# E-16_LVDS_to_HDMI.net
KiCad netlist of a schematic drawn in Altium Designer
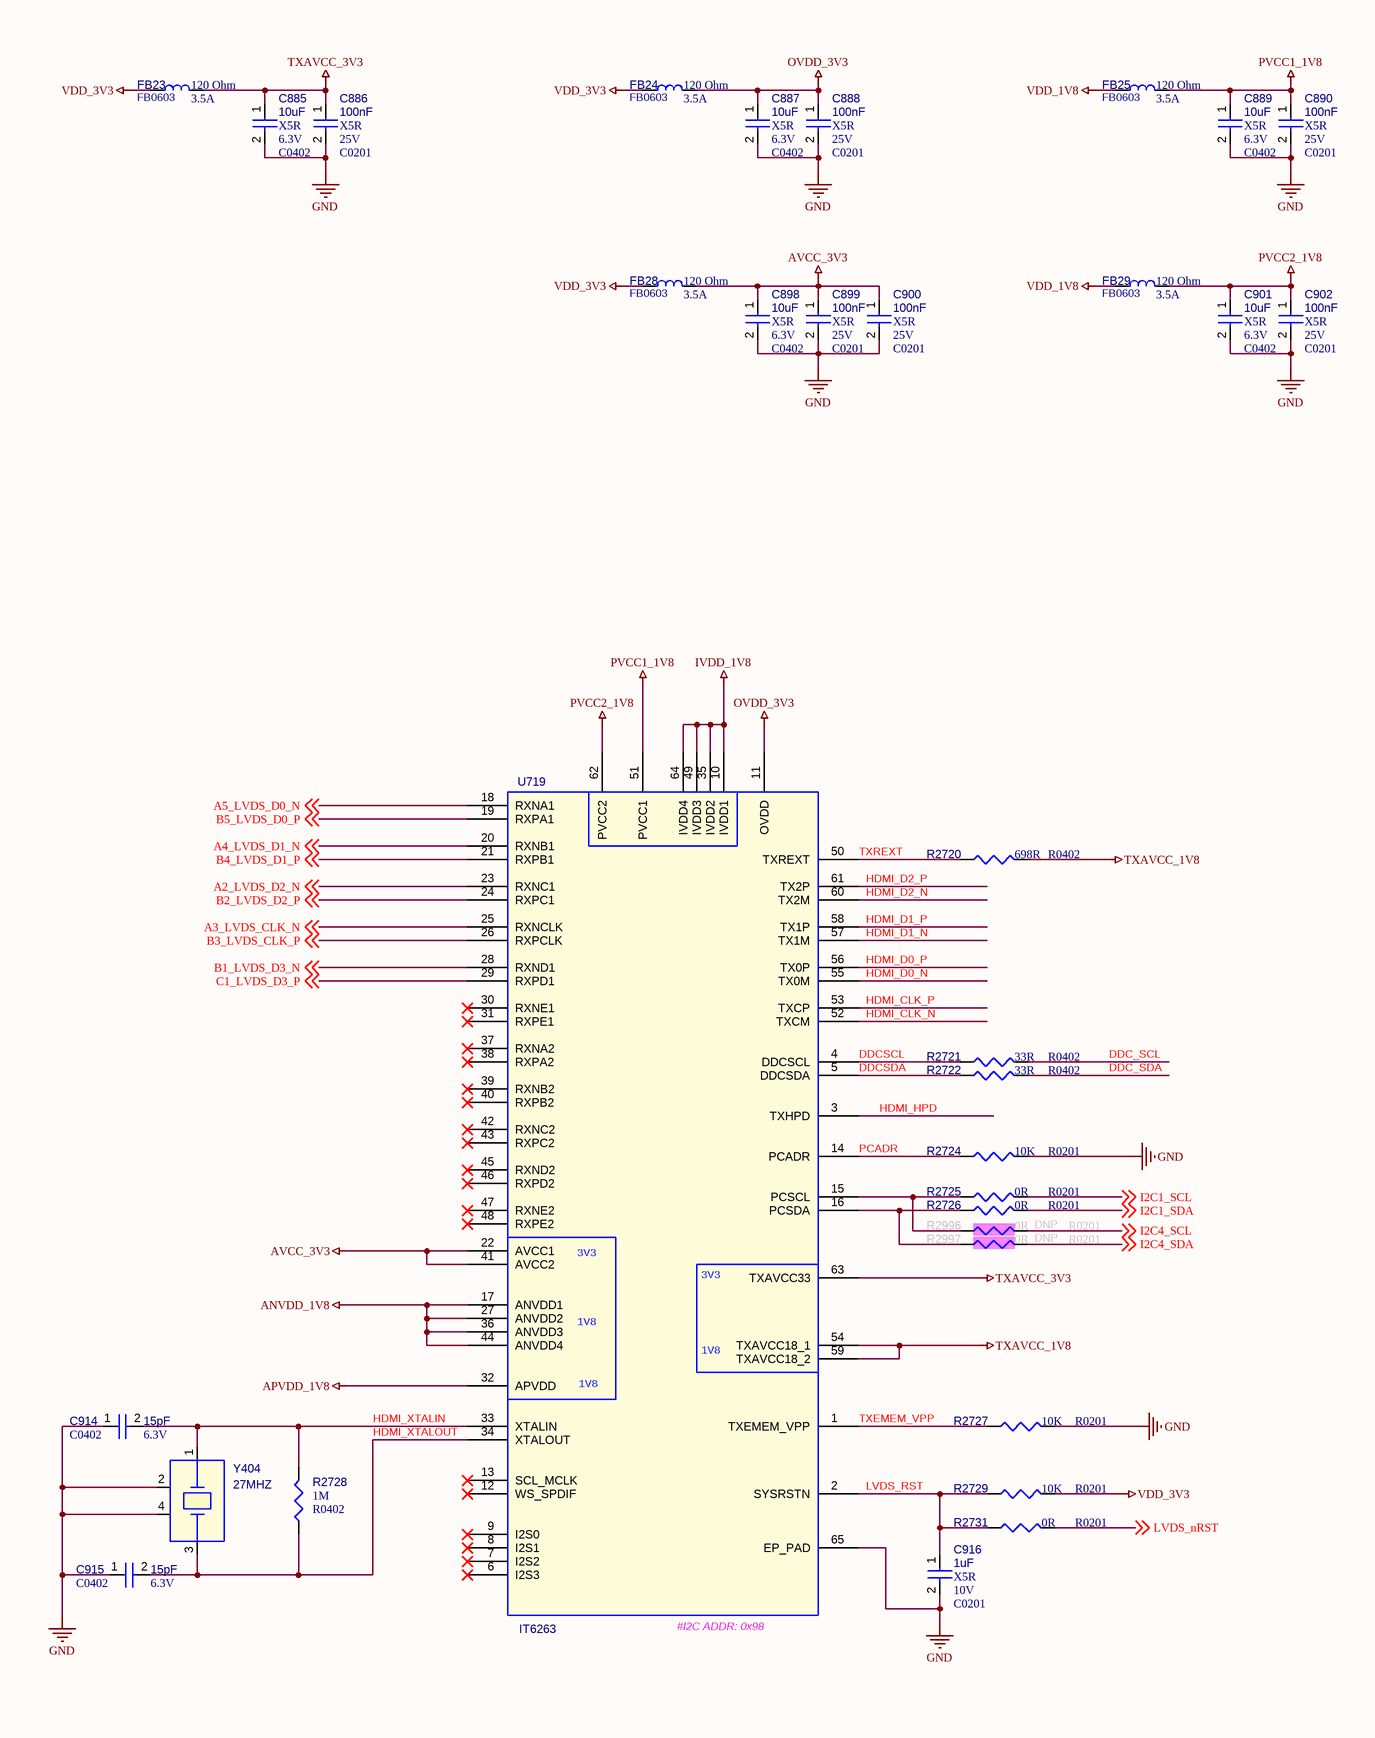
[diagram p0: E-16 LVDS to HDMI.SchDoc, left]
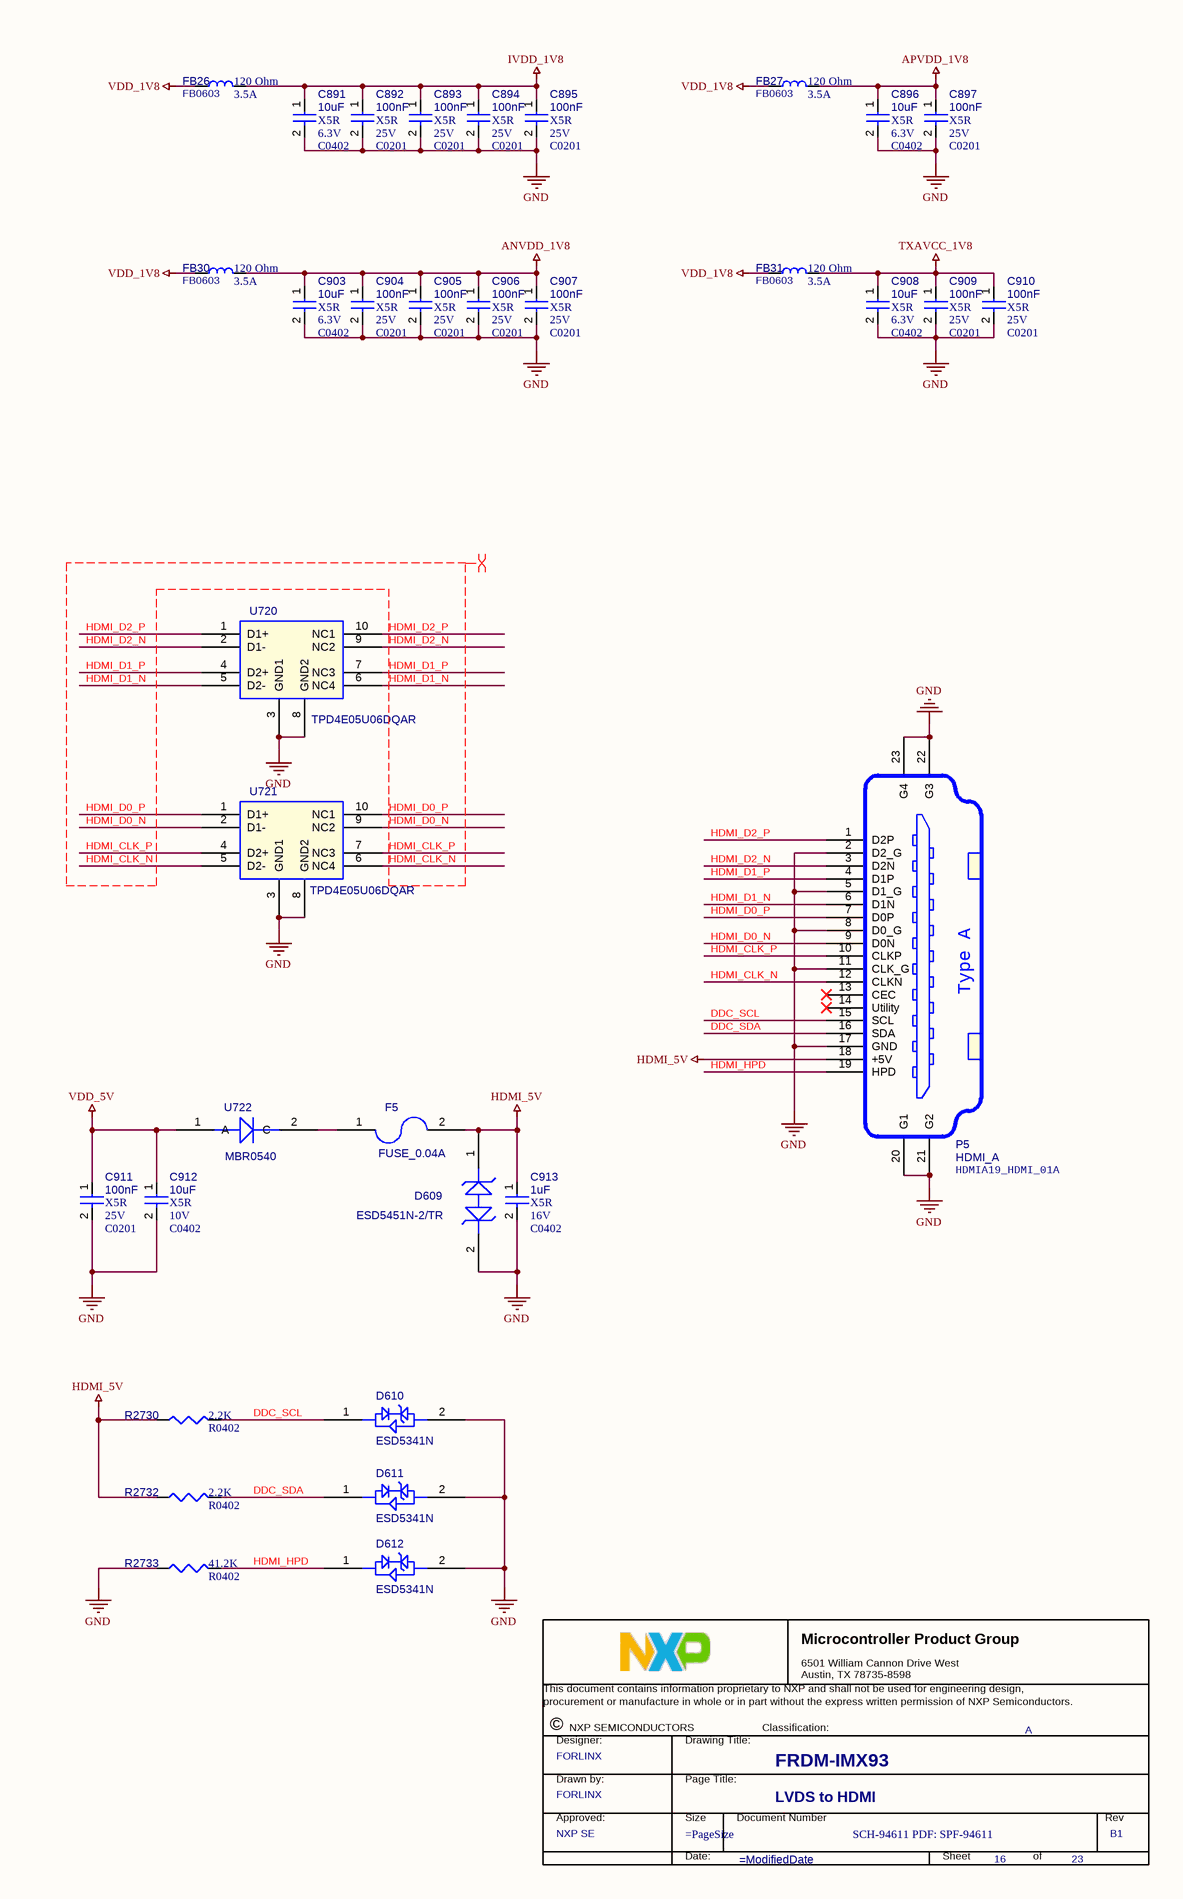
[diagram p1: E-16 LVDS to HDMI.SchDoc, right]

(export (version "E")
  (design (tool "Eeschema 10.0.6"))
  (components
    (comp (ref "C885")
      (value "10uF")
      (footprint "C0402")
      (description "0402,10uF,6.3V,+/-20%,X5R")
      (fields
        (field (name "VOLTAGE") "6.3V")
        (field (name "PCB FOOTPRINT") "C0402")
        (field (name "DIELECTRIC") "X5R")
        (field (name "MANUFACTURER") "FH(风华)")
        (field (name "TOLERANCE") "±10%")
        (field (name "CREATED BY") "JJJ")
      )
      (libsource (lib "*") (part "CAP NP"))
    )
    (comp (ref "C886")
      (value "100nF")
      (footprint "C0201")
      (description "0201,100nF,25V,+/-10%,X5R")
      (fields
        (field (name "VOLTAGE") "25V")
        (field (name "PCB FOOTPRINT") "C0201")
        (field (name "DIELECTRIC") "X5R")
        (field (name "TOLERANCE") "±10%")
        (field (name "MANUFACTURER") "FH(风华)")
        (field (name "CREATED BY") "JJJ")
      )
      (libsource (lib "*") (part "CAP NP"))
    )
    (comp (ref "C887")
      (value "10uF")
      (footprint "C0402")
      (description "0402,10uF,6.3V,+/-20%,X5R")
      (fields
        (field (name "VOLTAGE") "6.3V")
        (field (name "PCB FOOTPRINT") "C0402")
        (field (name "DIELECTRIC") "X5R")
        (field (name "MANUFACTURER") "FH(风华)")
        (field (name "TOLERANCE") "±10%")
        (field (name "CREATED BY") "JJJ")
      )
      (libsource (lib "*") (part "CAP NP"))
    )
    (comp (ref "C888")
      (value "100nF")
      (footprint "C0201")
      (description "0201,100nF,25V,+/-10%,X5R")
      (fields
        (field (name "VOLTAGE") "25V")
        (field (name "PCB FOOTPRINT") "C0201")
        (field (name "DIELECTRIC") "X5R")
        (field (name "TOLERANCE") "±10%")
        (field (name "MANUFACTURER") "FH(风华)")
        (field (name "CREATED BY") "JJJ")
      )
      (libsource (lib "*") (part "CAP NP"))
    )
    (comp (ref "C889")
      (value "10uF")
      (footprint "C0402")
      (description "0402,10uF,6.3V,+/-20%,X5R")
      (fields
        (field (name "VOLTAGE") "6.3V")
        (field (name "PCB FOOTPRINT") "C0402")
        (field (name "DIELECTRIC") "X5R")
        (field (name "MANUFACTURER") "FH(风华)")
        (field (name "TOLERANCE") "±10%")
        (field (name "CREATED BY") "JJJ")
      )
      (libsource (lib "*") (part "CAP NP"))
    )
    (comp (ref "C890")
      (value "100nF")
      (footprint "C0201")
      (description "0201,100nF,25V,+/-10%,X5R")
      (fields
        (field (name "VOLTAGE") "25V")
        (field (name "PCB FOOTPRINT") "C0201")
        (field (name "DIELECTRIC") "X5R")
        (field (name "TOLERANCE") "±10%")
        (field (name "MANUFACTURER") "FH(风华)")
        (field (name "CREATED BY") "JJJ")
      )
      (libsource (lib "*") (part "CAP NP"))
    )
    (comp (ref "C891")
      (value "10uF")
      (footprint "C0402")
      (description "0402,10uF,6.3V,+/-20%,X5R")
      (fields
        (field (name "VOLTAGE") "6.3V")
        (field (name "PCB FOOTPRINT") "C0402")
        (field (name "DIELECTRIC") "X5R")
        (field (name "MANUFACTURER") "FH(风华)")
        (field (name "TOLERANCE") "±10%")
        (field (name "CREATED BY") "JJJ")
      )
      (libsource (lib "*") (part "CAP NP"))
    )
    (comp (ref "C892")
      (value "100nF")
      (footprint "C0201")
      (description "0201,100nF,25V,+/-10%,X5R")
      (fields
        (field (name "VOLTAGE") "25V")
        (field (name "PCB FOOTPRINT") "C0201")
        (field (name "DIELECTRIC") "X5R")
        (field (name "TOLERANCE") "±10%")
        (field (name "MANUFACTURER") "FH(风华)")
        (field (name "CREATED BY") "JJJ")
      )
      (libsource (lib "*") (part "CAP NP"))
    )
    (comp (ref "C893")
      (value "100nF")
      (footprint "C0201")
      (description "0201,100nF,25V,+/-10%,X5R")
      (fields
        (field (name "VOLTAGE") "25V")
        (field (name "PCB FOOTPRINT") "C0201")
        (field (name "DIELECTRIC") "X5R")
        (field (name "MANUFACTURER") "FH(风华)")
        (field (name "TOLERANCE") "±10%")
        (field (name "CREATED BY") "JJJ")
      )
      (libsource (lib "*") (part "CAP NP"))
    )
    (comp (ref "C894")
      (value "100nF")
      (footprint "C0201")
      (description "0201,100nF,25V,+/-10%,X5R")
      (fields
        (field (name "VOLTAGE") "25V")
        (field (name "PCB FOOTPRINT") "C0201")
        (field (name "DIELECTRIC") "X5R")
        (field (name "MANUFACTURER") "FH(风华)")
        (field (name "TOLERANCE") "±10%")
        (field (name "CREATED BY") "JJJ")
      )
      (libsource (lib "*") (part "CAP NP"))
    )
    (comp (ref "C895")
      (value "100nF")
      (footprint "C0201")
      (description "0201,100nF,25V,+/-10%,X5R")
      (fields
        (field (name "VOLTAGE") "25V")
        (field (name "PCB FOOTPRINT") "C0201")
        (field (name "DIELECTRIC") "X5R")
        (field (name "TOLERANCE") "±10%")
        (field (name "MANUFACTURER") "FH(风华)")
        (field (name "CREATED BY") "JJJ")
      )
      (libsource (lib "*") (part "CAP NP"))
    )
    (comp (ref "C896")
      (value "10uF")
      (footprint "C0402")
      (description "0402,10uF,6.3V,+/-20%,X5R")
      (fields
        (field (name "VOLTAGE") "6.3V")
        (field (name "PCB FOOTPRINT") "C0402")
        (field (name "DIELECTRIC") "X5R")
        (field (name "MANUFACTURER") "FH(风华)")
        (field (name "TOLERANCE") "±10%")
        (field (name "CREATED BY") "JJJ")
      )
      (libsource (lib "*") (part "CAP NP"))
    )
    (comp (ref "C897")
      (value "100nF")
      (footprint "C0201")
      (description "0201,100nF,25V,+/-10%,X5R")
      (fields
        (field (name "VOLTAGE") "25V")
        (field (name "PCB FOOTPRINT") "C0201")
        (field (name "DIELECTRIC") "X5R")
        (field (name "MANUFACTURER") "FH(风华)")
        (field (name "TOLERANCE") "±10%")
        (field (name "CREATED BY") "JJJ")
      )
      (libsource (lib "*") (part "CAP NP"))
    )
    (comp (ref "C898")
      (value "10uF")
      (footprint "C0402")
      (description "0402,10uF,6.3V,+/-20%,X5R")
      (fields
        (field (name "VOLTAGE") "6.3V")
        (field (name "PCB FOOTPRINT") "C0402")
        (field (name "DIELECTRIC") "X5R")
        (field (name "TOLERANCE") "±10%")
        (field (name "MANUFACTURER") "FH(风华)")
        (field (name "CREATED BY") "JJJ")
      )
      (libsource (lib "*") (part "CAP NP"))
    )
    (comp (ref "C899")
      (value "100nF")
      (footprint "C0201")
      (description "0201,100nF,25V,+/-10%,X5R")
      (fields
        (field (name "VOLTAGE") "25V")
        (field (name "PCB FOOTPRINT") "C0201")
        (field (name "DIELECTRIC") "X5R")
        (field (name "MANUFACTURER") "FH(风华)")
        (field (name "TOLERANCE") "±10%")
        (field (name "CREATED BY") "JJJ")
      )
      (libsource (lib "*") (part "CAP NP"))
    )
    (comp (ref "C900")
      (value "100nF")
      (footprint "C0201")
      (description "0201,100nF,25V,+/-10%,X5R")
      (fields
        (field (name "VOLTAGE") "25V")
        (field (name "PCB FOOTPRINT") "C0201")
        (field (name "DIELECTRIC") "X5R")
        (field (name "MANUFACTURER") "FH(风华)")
        (field (name "TOLERANCE") "±10%")
        (field (name "CREATED BY") "JJJ")
      )
      (libsource (lib "*") (part "CAP NP"))
    )
    (comp (ref "C901")
      (value "10uF")
      (footprint "C0402")
      (description "0402,10uF,6.3V,+/-20%,X5R")
      (fields
        (field (name "VOLTAGE") "6.3V")
        (field (name "PCB FOOTPRINT") "C0402")
        (field (name "DIELECTRIC") "X5R")
        (field (name "TOLERANCE") "±10%")
        (field (name "MANUFACTURER") "FH(风华)")
        (field (name "CREATED BY") "JJJ")
      )
      (libsource (lib "*") (part "CAP NP"))
    )
    (comp (ref "C902")
      (value "100nF")
      (footprint "C0201")
      (description "0201,100nF,25V,+/-10%,X5R")
      (fields
        (field (name "VOLTAGE") "25V")
        (field (name "PCB FOOTPRINT") "C0201")
        (field (name "DIELECTRIC") "X5R")
        (field (name "MANUFACTURER") "FH(风华)")
        (field (name "TOLERANCE") "±10%")
        (field (name "CREATED BY") "JJJ")
      )
      (libsource (lib "*") (part "CAP NP"))
    )
    (comp (ref "C903")
      (value "10uF")
      (footprint "C0402")
      (description "0402,10uF,6.3V,+/-20%,X5R")
      (fields
        (field (name "VOLTAGE") "6.3V")
        (field (name "PCB FOOTPRINT") "C0402")
        (field (name "DIELECTRIC") "X5R")
        (field (name "MANUFACTURER") "FH(风华)")
        (field (name "TOLERANCE") "±10%")
        (field (name "CREATED BY") "JJJ")
      )
      (libsource (lib "*") (part "CAP NP"))
    )
    (comp (ref "C904")
      (value "100nF")
      (footprint "C0201")
      (description "0201,100nF,25V,+/-10%,X5R")
      (fields
        (field (name "VOLTAGE") "25V")
        (field (name "PCB FOOTPRINT") "C0201")
        (field (name "DIELECTRIC") "X5R")
        (field (name "TOLERANCE") "±10%")
        (field (name "MANUFACTURER") "FH(风华)")
        (field (name "CREATED BY") "JJJ")
      )
      (libsource (lib "*") (part "CAP NP"))
    )
    (comp (ref "C905")
      (value "100nF")
      (footprint "C0201")
      (description "0201,100nF,25V,+/-10%,X5R")
      (fields
        (field (name "VOLTAGE") "25V")
        (field (name "PCB FOOTPRINT") "C0201")
        (field (name "DIELECTRIC") "X5R")
        (field (name "MANUFACTURER") "FH(风华)")
        (field (name "TOLERANCE") "±10%")
        (field (name "CREATED BY") "JJJ")
      )
      (libsource (lib "*") (part "CAP NP"))
    )
    (comp (ref "C906")
      (value "100nF")
      (footprint "C0201")
      (description "0201,100nF,25V,+/-10%,X5R")
      (fields
        (field (name "VOLTAGE") "25V")
        (field (name "PCB FOOTPRINT") "C0201")
        (field (name "DIELECTRIC") "X5R")
        (field (name "MANUFACTURER") "FH(风华)")
        (field (name "TOLERANCE") "±10%")
        (field (name "CREATED BY") "JJJ")
      )
      (libsource (lib "*") (part "CAP NP"))
    )
    (comp (ref "C907")
      (value "100nF")
      (footprint "C0201")
      (description "0201,100nF,25V,+/-10%,X5R")
      (fields
        (field (name "VOLTAGE") "25V")
        (field (name "PCB FOOTPRINT") "C0201")
        (field (name "DIELECTRIC") "X5R")
        (field (name "TOLERANCE") "±10%")
        (field (name "MANUFACTURER") "FH(风华)")
        (field (name "CREATED BY") "JJJ")
      )
      (libsource (lib "*") (part "CAP NP"))
    )
    (comp (ref "C908")
      (value "10uF")
      (footprint "C0402")
      (description "0402,10uF,6.3V,+/-20%,X5R")
      (fields
        (field (name "VOLTAGE") "6.3V")
        (field (name "PCB FOOTPRINT") "C0402")
        (field (name "DIELECTRIC") "X5R")
        (field (name "MANUFACTURER") "FH(风华)")
        (field (name "TOLERANCE") "±10%")
        (field (name "CREATED BY") "JJJ")
      )
      (libsource (lib "*") (part "CAP NP"))
    )
    (comp (ref "C909")
      (value "100nF")
      (footprint "C0201")
      (description "0201,100nF,25V,+/-10%,X5R")
      (fields
        (field (name "VOLTAGE") "25V")
        (field (name "PCB FOOTPRINT") "C0201")
        (field (name "DIELECTRIC") "X5R")
        (field (name "TOLERANCE") "±10%")
        (field (name "MANUFACTURER") "FH(风华)")
        (field (name "CREATED BY") "JJJ")
      )
      (libsource (lib "*") (part "CAP NP"))
    )
    (comp (ref "C910")
      (value "100nF")
      (footprint "C0201")
      (description "0201,100nF,25V,+/-10%,X5R")
      (fields
        (field (name "VOLTAGE") "25V")
        (field (name "PCB FOOTPRINT") "C0201")
        (field (name "DIELECTRIC") "X5R")
        (field (name "TOLERANCE") "±10%")
        (field (name "MANUFACTURER") "FH(风华)")
        (field (name "CREATED BY") "JJJ")
      )
      (libsource (lib "*") (part "CAP NP"))
    )
    (comp (ref "C911")
      (value "100nF")
      (footprint "C0201")
      (description "0201,100nF,25V,+/-10%,X5R")
      (fields
        (field (name "VOLTAGE") "25V")
        (field (name "PCB FOOTPRINT") "C0201")
        (field (name "DIELECTRIC") "X5R")
        (field (name "MANUFACTURER") "FH(风华)")
        (field (name "TOLERANCE") "±10%")
        (field (name "CREATED BY") "JJJ")
      )
      (libsource (lib "*") (part "CAP NP"))
    )
    (comp (ref "C912")
      (value "10uF")
      (footprint "C0402")
      (description "0402,10uF,6.3V,+/-20%,X5R")
      (fields
        (field (name "VOLTAGE") "10V")
        (field (name "PCB FOOTPRINT") "C0402")
        (field (name "DIELECTRIC") "X5R")
        (field (name "MANUFACTURER") "FH(风华)")
        (field (name "TOLERANCE") "±10%")
        (field (name "CREATED BY") "JJJ")
      )
      (libsource (lib "*") (part "CAP NP"))
    )
    (comp (ref "C913")
      (value "1uF")
      (footprint "C0402")
      (description "0402,1uF,16V,+/-10%,X5R")
      (fields
        (field (name "VOLTAGE") "16V")
        (field (name "PCB FOOTPRINT") "C0402")
        (field (name "DIELECTRIC") "X5R")
        (field (name "TOLERANCE") "±10%")
        (field (name "MANUFACTURER") "FH(风华)")
        (field (name "CREATED BY") "JJJ")
      )
      (libsource (lib "*") (part "CAP NP"))
    )
    (comp (ref "C914")
      (value "15pF")
      (footprint "C0402")
      (description "0402,15pF,50V,+/-5%,NPO")
      (fields
        (field (name "VOLTAGE") "6.3V")
        (field (name "PCB FOOTPRINT") "C0402")
        (field (name "TOLERANCE") "±10%")
        (field (name "MANUFACTURER") "FH(风华)")
        (field (name "CREATED BY") "JJJ")
      )
      (libsource (lib "*") (part "CAP NP"))
    )
    (comp (ref "C915")
      (value "15pF")
      (footprint "C0402")
      (description "0402,15pF,50V,+/-5%,NPO")
      (fields
        (field (name "VOLTAGE") "6.3V")
        (field (name "PCB FOOTPRINT") "C0402")
        (field (name "TOLERANCE") "±10%")
        (field (name "MANUFACTURER") "FH(风华)")
        (field (name "CREATED BY") "JJJ")
      )
      (libsource (lib "*") (part "CAP NP"))
    )
    (comp (ref "C916")
      (value "1uF")
      (footprint "C0201")
      (description "0201,1uF,10V,+/-20%,X5R")
      (fields
        (field (name "VOLTAGE") "10V")
        (field (name "PCB FOOTPRINT") "C0201")
        (field (name "DIELECTRIC") "X5R")
        (field (name "MANUFACTURER") "FH(风华)")
        (field (name "TOLERANCE") "±10%")
        (field (name "CREATED BY") "JJJ")
      )
      (libsource (lib "*") (part "CAP NP"))
    )
    (comp (ref "D609")
      (value "ESD5451N-2/TR")
      (footprint "0402TVS")
      (libsource (lib "*") (part "ESD5451N-2/TR"))
    )
    (comp (ref "D610")
      (value "ESD5341N")
      (footprint "0402TVS")
      (description "ESD5341N-2/TR")
      (libsource (lib "*") (part "ESD5341N"))
    )
    (comp (ref "D611")
      (value "ESD5341N")
      (footprint "0402TVS")
      (description "ESD5341N-2/TR")
      (libsource (lib "*") (part "ESD5341N"))
    )
    (comp (ref "D612")
      (value "ESD5341N")
      (footprint "0402TVS")
      (description "ESD5341N-2/TR")
      (libsource (lib "*") (part "ESD5341N"))
    )
    (comp (ref "F5")
      (value "FUSE_0.04A")
      (footprint "F0603")
      (description "0603,0.04A/0.12A,15V,ASMD0603-004")
      (libsource (lib "*") (part "FUSE_0.5A"))
    )
    (comp (ref "FB23")
      (value "120 Ohm")
      (footprint "FB0603")
      (description "0603,120Ohm@100MHZ,3A")
      (fields (field (name "ELECTRIC CURRENT") "3.5A") (field (name "PCB FOOTPRINT") "FB0603"))
      (libsource (lib "*") (part "FB0402,120ohm,1.3A"))
    )
    (comp (ref "FB24")
      (value "120 Ohm")
      (footprint "FB0603")
      (description "0603,120Ohm@100MHZ,3A")
      (fields (field (name "ELECTRIC CURRENT") "3.5A") (field (name "PCB FOOTPRINT") "FB0603"))
      (libsource (lib "*") (part "FB0402,120ohm,1.3A"))
    )
    (comp (ref "FB25")
      (value "120 Ohm")
      (footprint "FB0603")
      (description "0603,120Ohm@100MHZ,3A")
      (fields (field (name "ELECTRIC CURRENT") "3.5A") (field (name "PCB FOOTPRINT") "FB0603"))
      (libsource (lib "*") (part "FB0402,120ohm,1.3A"))
    )
    (comp (ref "FB26")
      (value "120 Ohm")
      (footprint "FB0603")
      (description "0603,120Ohm@100MHZ,3A")
      (fields (field (name "ELECTRIC CURRENT") "3.5A") (field (name "PCB FOOTPRINT") "FB0603"))
      (libsource (lib "*") (part "FB0402,120ohm,1.3A"))
    )
    (comp (ref "FB27")
      (value "120 Ohm")
      (footprint "FB0603")
      (description "0603,120Ohm@100MHZ,3A")
      (fields (field (name "ELECTRIC CURRENT") "3.5A") (field (name "PCB FOOTPRINT") "FB0603"))
      (libsource (lib "*") (part "FB0402,120ohm,1.3A"))
    )
    (comp (ref "FB28")
      (value "120 Ohm")
      (footprint "FB0603")
      (description "0603,120Ohm@100MHZ,3A")
      (fields (field (name "ELECTRIC CURRENT") "3.5A") (field (name "PCB FOOTPRINT") "FB0603"))
      (libsource (lib "*") (part "FB0402,120ohm,1.3A"))
    )
    (comp (ref "FB29")
      (value "120 Ohm")
      (footprint "FB0603")
      (description "0603,120Ohm@100MHZ,3A")
      (fields (field (name "ELECTRIC CURRENT") "3.5A") (field (name "PCB FOOTPRINT") "FB0603"))
      (libsource (lib "*") (part "FB0402,120ohm,1.3A"))
    )
    (comp (ref "FB30")
      (value "120 Ohm")
      (footprint "FB0603")
      (description "0603,120Ohm@100MHZ,3A")
      (fields (field (name "ELECTRIC CURRENT") "3.5A") (field (name "PCB FOOTPRINT") "FB0603"))
      (libsource (lib "*") (part "FB0402,120ohm,1.3A"))
    )
    (comp (ref "FB31")
      (value "120 Ohm")
      (footprint "FB0603")
      (description "0603,120Ohm@100MHZ,3A")
      (fields (field (name "ELECTRIC CURRENT") "3.5A") (field (name "PCB FOOTPRINT") "FB0603"))
      (libsource (lib "*") (part "FB0402,120ohm,1.3A"))
    )
    (comp (ref "P5")
      (value "HDMI_A")
      (footprint "HDMIA19_HDMI_01A")
      (description "HDMI-A")
      (fields
        (field (name "MANUFACTURER") "旺科达")
        (field (name "MANUFACTURER PART NUMBER") "HDMI_01A")
        (field (name "PCB FOOTPRINT") "HDMIA19_HDMI_01A")
        (field (name "CREATED BY") "JJJ")
      )
      (libsource (lib "*") (part "HDMI_A"))
    )
    (comp (ref "R2720")
      (value "698R")
      (footprint "R0402")
      (description "0402,698Ohm,+/-1%")
      (fields (field (name "PCB FOOTPRINT") "R0402"))
      (libsource (lib "*") (part "R0402,4.7K_Dup1"))
    )
    (comp (ref "R2721")
      (value "33R")
      (footprint "R0402")
      (description "0402,33Ohm,+/-1%")
      (fields (field (name "PCB FOOTPRINT") "R0402"))
      (libsource (lib "*") (part "R0402,4.7K_Dup1"))
    )
    (comp (ref "R2722")
      (value "33R")
      (footprint "R0402")
      (description "0402,33Ohm,+/-1%")
      (fields (field (name "PCB FOOTPRINT") "R0402"))
      (libsource (lib "*") (part "R0402,4.7K_Dup1"))
    )
    (comp (ref "R2724")
      (value "10K")
      (footprint "R0201")
      (description "0201,10K,+/-5%")
      (fields (field (name "PCB FOOTPRINT") "R0201"))
      (libsource (lib "*") (part "R0402,4.7K_Dup1"))
    )
    (comp (ref "R2725")
      (value "0R")
      (footprint "R0201")
      (description "0201,0Ohm,+/-5%")
      (fields (field (name "PCB FOOTPRINT") "R0201"))
      (libsource (lib "*") (part "R0402,4.7K_Dup1"))
    )
    (comp (ref "R2726")
      (value "0R")
      (footprint "R0201")
      (description "0201,0Ohm,+/-5%")
      (fields (field (name "PCB FOOTPRINT") "R0201"))
      (libsource (lib "*") (part "R0402,4.7K_Dup1"))
    )
    (comp (ref "R2727")
      (value "10K")
      (footprint "R0201")
      (description "0201,10K,+/-5%")
      (fields (field (name "PCB FOOTPRINT") "R0201"))
      (libsource (lib "*") (part "R0402,4.7K_Dup1"))
    )
    (comp (ref "R2728")
      (value "1M")
      (footprint "R0402")
      (description "0402,1M,+/-1%")
      (fields (field (name "PCB FOOTPRINT") "R0402"))
      (libsource (lib "*") (part "R0402,4.7K_Dup1"))
    )
    (comp (ref "R2729")
      (value "10K")
      (footprint "R0201")
      (description "0201,10K,+/-5%")
      (fields (field (name "PCB FOOTPRINT") "R0201"))
      (libsource (lib "*") (part "R0402,4.7K_Dup1"))
    )
    (comp (ref "R2730")
      (value "2.2K")
      (footprint "R0402")
      (description "0402,2.2K,+/-1%")
      (fields (field (name "PCB FOOTPRINT") "R0402"))
      (libsource (lib "*") (part "R0402,4.7K_Dup1"))
    )
    (comp (ref "R2731")
      (value "0R")
      (footprint "R0201")
      (description "0201,0Ohm,+/-5%")
      (fields (field (name "PCB FOOTPRINT") "R0201"))
      (libsource (lib "*") (part "R0402,4.7K_Dup1"))
    )
    (comp (ref "R2732")
      (value "2.2K")
      (footprint "R0402")
      (description "0402,2.2K,+/-1%")
      (fields (field (name "PCB FOOTPRINT") "R0402"))
      (libsource (lib "*") (part "R0402,4.7K_Dup1"))
    )
    (comp (ref "R2733")
      (value "41.2K")
      (footprint "R0402")
      (description "0402,41.2K,+/-1%")
      (fields (field (name "PCB FOOTPRINT") "R0402"))
      (libsource (lib "*") (part "R0402,4.7K_Dup1"))
    )
    (comp (ref "R2996")
      (value "0R")
      (footprint "R0201")
      (description "0201,0Ohm,+/-5%")
      (fields (field (name "PCB FOOTPRINT") "R0201") (field (name "ASSY_OPT") "DNP"))
      (libsource (lib "*") (part "R0402,4.7K_Dup1"))
    )
    (comp (ref "R2997")
      (value "0R")
      (footprint "R0201")
      (description "0201,0Ohm,+/-5%")
      (fields (field (name "PCB FOOTPRINT") "R0201") (field (name "ASSY_OPT") "DNP"))
      (libsource (lib "*") (part "R0402,4.7K_Dup1"))
    )
    (comp (ref "U719")
      (value "IT6263")
      (footprint "qfn64_0p5_9x9_157ep")
      (description "IT6263FN,QFN64,9*9mm,LVDS to HDMI")
      (libsource (lib "*") (part "IT6263"))
    )
    (comp (ref "U720")
      (value "TPD4E05U06DQAR")
      (footprint "USON-10")
      (description "TPD4E05U06DQAR,USON")
      (libsource (lib "*") (part "TPD4E05U06DQAR_10"))
    )
    (comp (ref "U721")
      (value "TPD4E05U06DQAR")
      (footprint "USON-10")
      (description "TPD4E05U06DQAR,USON")
      (libsource (lib "*") (part "TPD4E05U06DQAR_5"))
    )
    (comp (ref "U722")
      (value "MBR0540")
      (footprint "SOD_123")
      (description "MBR0540,SOD123")
      (libsource (lib "*") (part "MBR0540_0"))
    )
    (comp (ref "Y404")
      (value "27MHZ")
      (footprint "xtlosc4_3p2x2p5mm_sm")
      (description "Crystal,27MHZ,4P,3.2*2.5mm,+/-20ppm,20pf")
      (libsource (lib "*") (part "XTAL_13"))
    )
  )
  (nets
    (net (code "1") (name "/DDCSCL") (class "Default")
      (node (ref "R2721") (pin "1") (pinfunction "1_1") (pintype "passive"))
      (node (ref "U719") (pin "4") (pinfunction "DDCSCL_4") (pintype "passive"))
    )
    (net (code "2") (name "/DDCSDA") (class "Default")
      (node (ref "R2722") (pin "1") (pinfunction "1_1") (pintype "passive"))
      (node (ref "U719") (pin "5") (pinfunction "DDCSDA_5") (pintype "passive"))
    )
    (net (code "3") (name "/DDC_SCL") (class "Default")
      (node (ref "D610") (pin "1") (pinfunction "1_1") (pintype "passive"))
      (node (ref "P5") (pin "15") (pinfunction "SCL_15") (pintype "passive"))
      (node (ref "R2721") (pin "2") (pinfunction "2_2") (pintype "passive"))
      (node (ref "R2730") (pin "2") (pinfunction "2_2") (pintype "passive"))
    )
    (net (code "4") (name "/DDC_SDA") (class "Default")
      (node (ref "D611") (pin "1") (pinfunction "1_1") (pintype "passive"))
      (node (ref "P5") (pin "16") (pinfunction "SDA_16") (pintype "passive"))
      (node (ref "R2722") (pin "2") (pinfunction "2_2") (pintype "passive"))
      (node (ref "R2732") (pin "2") (pinfunction "2_2") (pintype "passive"))
    )
    (net (code "5") (name "/HDMI_CLK_N") (class "Default")
      (node (ref "P5") (pin "12") (pinfunction "CLKN_12") (pintype "passive"))
      (node (ref "U719") (pin "52") (pinfunction "TXCM_52") (pintype "passive"))
      (node (ref "U721") (pin "5") (pinfunction "D2-_5") (pintype "passive"))
      (node (ref "U721") (pin "6") (pinfunction "NC4_6") (pintype "passive"))
    )
    (net (code "6") (name "/HDMI_CLK_P") (class "Default")
      (node (ref "P5") (pin "10") (pinfunction "CLKP_10") (pintype "passive"))
      (node (ref "U719") (pin "53") (pinfunction "TXCP_53") (pintype "passive"))
      (node (ref "U721") (pin "4") (pinfunction "D2+_4") (pintype "passive"))
      (node (ref "U721") (pin "7") (pinfunction "NC3_7") (pintype "passive"))
    )
    (net (code "7") (name "/HDMI_D0_N") (class "Default")
      (node (ref "P5") (pin "9") (pinfunction "D0N_9") (pintype "passive"))
      (node (ref "U719") (pin "55") (pinfunction "TX0M_55") (pintype "passive"))
      (node (ref "U721") (pin "2") (pinfunction "D1-_2") (pintype "passive"))
      (node (ref "U721") (pin "9") (pinfunction "NC2_9") (pintype "passive"))
    )
    (net (code "8") (name "/HDMI_D0_P") (class "Default")
      (node (ref "P5") (pin "7") (pinfunction "D0P_7") (pintype "passive"))
      (node (ref "U719") (pin "56") (pinfunction "TX0P_56") (pintype "passive"))
      (node (ref "U721") (pin "1") (pinfunction "D1+_1") (pintype "passive"))
      (node (ref "U721") (pin "10") (pinfunction "NC1_10") (pintype "passive"))
    )
    (net (code "9") (name "/HDMI_D1_N") (class "Default")
      (node (ref "P5") (pin "6") (pinfunction "D1N_6") (pintype "passive"))
      (node (ref "U719") (pin "57") (pinfunction "TX1M_57") (pintype "passive"))
      (node (ref "U720") (pin "5") (pinfunction "D2-_5") (pintype "passive"))
      (node (ref "U720") (pin "6") (pinfunction "NC4_6") (pintype "passive"))
    )
    (net (code "10") (name "/HDMI_D1_P") (class "Default")
      (node (ref "P5") (pin "4") (pinfunction "D1P_4") (pintype "passive"))
      (node (ref "U719") (pin "58") (pinfunction "TX1P_58") (pintype "passive"))
      (node (ref "U720") (pin "4") (pinfunction "D2+_4") (pintype "passive"))
      (node (ref "U720") (pin "7") (pinfunction "NC3_7") (pintype "passive"))
    )
    (net (code "11") (name "/HDMI_D2_N") (class "Default")
      (node (ref "P5") (pin "3") (pinfunction "D2N_3") (pintype "passive"))
      (node (ref "U719") (pin "60") (pinfunction "TX2M_60") (pintype "passive"))
      (node (ref "U720") (pin "2") (pinfunction "D1-_2") (pintype "passive"))
      (node (ref "U720") (pin "9") (pinfunction "NC2_9") (pintype "passive"))
    )
    (net (code "12") (name "/HDMI_D2_P") (class "Default")
      (node (ref "P5") (pin "1") (pinfunction "D2P_1") (pintype "passive"))
      (node (ref "U719") (pin "61") (pinfunction "TX2P_61") (pintype "passive"))
      (node (ref "U720") (pin "1") (pinfunction "D1+_1") (pintype "passive"))
      (node (ref "U720") (pin "10") (pinfunction "NC1_10") (pintype "passive"))
    )
    (net (code "13") (name "/HDMI_HPD") (class "Default")
      (node (ref "D612") (pin "1") (pinfunction "1_1") (pintype "passive"))
      (node (ref "P5") (pin "19") (pinfunction "HPD_19") (pintype "passive"))
      (node (ref "R2733") (pin "2") (pinfunction "2_2") (pintype "passive"))
      (node (ref "U719") (pin "3") (pinfunction "TXHPD_3") (pintype "passive"))
    )
    (net (code "14") (name "/HDMI_XTALIN") (class "Default")
      (node (ref "C914") (pin "2") (pinfunction "2_2") (pintype "passive"))
      (node (ref "R2728") (pin "2") (pinfunction "2_2") (pintype "passive"))
      (node (ref "U719") (pin "33") (pinfunction "XTALIN_33") (pintype "passive"))
      (node (ref "Y404") (pin "1") (pinfunction "1_1") (pintype "passive"))
    )
    (net (code "15") (name "/HDMI_XTALOUT") (class "Default")
      (node (ref "C915") (pin "2") (pinfunction "2_2") (pintype "passive"))
      (node (ref "R2728") (pin "1") (pinfunction "1_1") (pintype "passive"))
      (node (ref "U719") (pin "34") (pinfunction "XTALOUT_34") (pintype "passive"))
      (node (ref "Y404") (pin "3") (pinfunction "3_3") (pintype "passive"))
    )
    (net (code "16") (name "/LVDS_RST") (class "Default")
      (node (ref "C916") (pin "1") (pinfunction "1_1") (pintype "passive"))
      (node (ref "R2729") (pin "1") (pinfunction "1_1") (pintype "passive"))
      (node (ref "R2731") (pin "1") (pinfunction "1_1") (pintype "passive"))
      (node (ref "U719") (pin "2") (pinfunction "SYSRSTN_2") (pintype "passive"))
    )
    (net (code "17") (name "/PCADR") (class "Default")
      (node (ref "R2724") (pin "1") (pinfunction "1_1") (pintype "passive"))
      (node (ref "U719") (pin "14") (pinfunction "PCADR_14") (pintype "passive"))
    )
    (net (code "18") (name "/TXEMEM_VPP") (class "Default")
      (node (ref "R2727") (pin "1") (pinfunction "1_1") (pintype "passive"))
      (node (ref "U719") (pin "1") (pinfunction "TXEMEM_VPP_1") (pintype "passive"))
    )
    (net (code "19") (name "/TXREXT") (class "Default")
      (node (ref "R2720") (pin "1") (pinfunction "1_1") (pintype "passive"))
      (node (ref "U719") (pin "50") (pinfunction "TXREXT_50") (pintype "passive"))
    )
    (net (code "20") (name "A2_LVDS_D2_N") (class "Default")
      (node (ref "U719") (pin "23") (pinfunction "RXNC1_23") (pintype "passive"))
    )
    (net (code "21") (name "A3_LVDS_CLK_N") (class "Default")
      (node (ref "U719") (pin "25") (pinfunction "RXNCLK_25") (pintype "passive"))
    )
    (net (code "22") (name "A4_LVDS_D1_N") (class "Default")
      (node (ref "U719") (pin "20") (pinfunction "RXNB1_20") (pintype "passive"))
    )
    (net (code "23") (name "A5_LVDS_D0_N") (class "Default")
      (node (ref "U719") (pin "18") (pinfunction "RXNA1_18") (pintype "passive"))
    )
    (net (code "24") (name "ANVDD_1V8") (class "Default")
      (node (ref "C903") (pin "1") (pinfunction "1_1") (pintype "passive"))
      (node (ref "C904") (pin "1") (pinfunction "1_1") (pintype "passive"))
      (node (ref "C905") (pin "1") (pinfunction "1_1") (pintype "passive"))
      (node (ref "C906") (pin "1") (pinfunction "1_1") (pintype "passive"))
      (node (ref "C907") (pin "1") (pinfunction "1_1") (pintype "passive"))
      (node (ref "FB30") (pin "2") (pinfunction "2_2") (pintype "passive"))
      (node (ref "U719") (pin "17") (pinfunction "ANVDD1_17") (pintype "passive"))
      (node (ref "U719") (pin "27") (pinfunction "ANVDD2_27") (pintype "passive"))
      (node (ref "U719") (pin "36") (pinfunction "ANVDD3_36") (pintype "passive"))
      (node (ref "U719") (pin "44") (pinfunction "ANVDD4_44") (pintype "passive"))
    )
    (net (code "25") (name "APVDD_1V8") (class "Default")
      (node (ref "C896") (pin "1") (pinfunction "1_1") (pintype "passive"))
      (node (ref "C897") (pin "1") (pinfunction "1_1") (pintype "passive"))
      (node (ref "FB27") (pin "2") (pinfunction "2_2") (pintype "passive"))
      (node (ref "U719") (pin "32") (pinfunction "APVDD_32") (pintype "passive"))
    )
    (net (code "26") (name "AVCC_3V3") (class "Default")
      (node (ref "C898") (pin "1") (pinfunction "1_1") (pintype "passive"))
      (node (ref "C899") (pin "1") (pinfunction "1_1") (pintype "passive"))
      (node (ref "C900") (pin "1") (pinfunction "1_1") (pintype "passive"))
      (node (ref "FB28") (pin "2") (pinfunction "2_2") (pintype "passive"))
      (node (ref "U719") (pin "22") (pinfunction "AVCC1_22") (pintype "passive"))
      (node (ref "U719") (pin "41") (pinfunction "AVCC2_41") (pintype "passive"))
    )
    (net (code "27") (name "B1_LVDS_D3_N") (class "Default")
      (node (ref "U719") (pin "28") (pinfunction "RXND1_28") (pintype "passive"))
    )
    (net (code "28") (name "B2_LVDS_D2_P") (class "Default")
      (node (ref "U719") (pin "24") (pinfunction "RXPC1_24") (pintype "passive"))
    )
    (net (code "29") (name "B3_LVDS_CLK_P") (class "Default")
      (node (ref "U719") (pin "26") (pinfunction "RXPCLK_26") (pintype "passive"))
    )
    (net (code "30") (name "B4_LVDS_D1_P") (class "Default")
      (node (ref "U719") (pin "21") (pinfunction "RXPB1_21") (pintype "passive"))
    )
    (net (code "31") (name "B5_LVDS_D0_P") (class "Default")
      (node (ref "U719") (pin "19") (pinfunction "RXPA1_19") (pintype "passive"))
    )
    (net (code "32") (name "C1_LVDS_D3_P") (class "Default")
      (node (ref "U719") (pin "29") (pinfunction "RXPD1_29") (pintype "passive"))
    )
    (net (code "33") (name "GND") (class "Default")
      (node (ref "C885") (pin "2") (pinfunction "2_2") (pintype "passive"))
      (node (ref "C886") (pin "2") (pinfunction "2_2") (pintype "passive"))
      (node (ref "C887") (pin "2") (pinfunction "2_2") (pintype "passive"))
      (node (ref "C888") (pin "2") (pinfunction "2_2") (pintype "passive"))
      (node (ref "C889") (pin "2") (pinfunction "2_2") (pintype "passive"))
      (node (ref "C890") (pin "2") (pinfunction "2_2") (pintype "passive"))
      (node (ref "C891") (pin "2") (pinfunction "2_2") (pintype "passive"))
      (node (ref "C892") (pin "2") (pinfunction "2_2") (pintype "passive"))
      (node (ref "C893") (pin "2") (pinfunction "2_2") (pintype "passive"))
      (node (ref "C894") (pin "2") (pinfunction "2_2") (pintype "passive"))
      (node (ref "C895") (pin "2") (pinfunction "2_2") (pintype "passive"))
      (node (ref "C896") (pin "2") (pinfunction "2_2") (pintype "passive"))
      (node (ref "C897") (pin "2") (pinfunction "2_2") (pintype "passive"))
      (node (ref "C898") (pin "2") (pinfunction "2_2") (pintype "passive"))
      (node (ref "C899") (pin "2") (pinfunction "2_2") (pintype "passive"))
      (node (ref "C900") (pin "2") (pinfunction "2_2") (pintype "passive"))
      (node (ref "C901") (pin "2") (pinfunction "2_2") (pintype "passive"))
      (node (ref "C902") (pin "2") (pinfunction "2_2") (pintype "passive"))
      (node (ref "C903") (pin "2") (pinfunction "2_2") (pintype "passive"))
      (node (ref "C904") (pin "2") (pinfunction "2_2") (pintype "passive"))
      (node (ref "C905") (pin "2") (pinfunction "2_2") (pintype "passive"))
      (node (ref "C906") (pin "2") (pinfunction "2_2") (pintype "passive"))
      (node (ref "C907") (pin "2") (pinfunction "2_2") (pintype "passive"))
      (node (ref "C908") (pin "2") (pinfunction "2_2") (pintype "passive"))
      (node (ref "C909") (pin "2") (pinfunction "2_2") (pintype "passive"))
      (node (ref "C910") (pin "2") (pinfunction "2_2") (pintype "passive"))
      (node (ref "C911") (pin "2") (pinfunction "2_2") (pintype "passive"))
      (node (ref "C912") (pin "2") (pinfunction "2_2") (pintype "passive"))
      (node (ref "C913") (pin "2") (pinfunction "2_2") (pintype "passive"))
      (node (ref "C914") (pin "1") (pinfunction "1_1") (pintype "passive"))
      (node (ref "C915") (pin "1") (pinfunction "1_1") (pintype "passive"))
      (node (ref "C916") (pin "2") (pinfunction "2_2") (pintype "passive"))
      (node (ref "D609") (pin "2") (pinfunction "2_2") (pintype "passive"))
      (node (ref "D610") (pin "2") (pinfunction "2_2") (pintype "passive"))
      (node (ref "D611") (pin "2") (pinfunction "2_2") (pintype "passive"))
      (node (ref "D612") (pin "2") (pinfunction "2_2") (pintype "passive"))
      (node (ref "P5") (pin "11") (pinfunction "CLK_G_11") (pintype "passive"))
      (node (ref "P5") (pin "17") (pinfunction "GND_17") (pintype "passive"))
      (node (ref "P5") (pin "2") (pinfunction "D2_G_2") (pintype "passive"))
      (node (ref "P5") (pin "20") (pinfunction "G1_20") (pintype "passive"))
      (node (ref "P5") (pin "21") (pinfunction "G2_21") (pintype "passive"))
      (node (ref "P5") (pin "22") (pinfunction "G3_22") (pintype "passive"))
      (node (ref "P5") (pin "23") (pinfunction "G4_23") (pintype "passive"))
      (node (ref "P5") (pin "5") (pinfunction "D1_G_5") (pintype "passive"))
      (node (ref "P5") (pin "8") (pinfunction "D0_G_8") (pintype "passive"))
      (node (ref "R2724") (pin "2") (pinfunction "2_2") (pintype "passive"))
      (node (ref "R2727") (pin "2") (pinfunction "2_2") (pintype "passive"))
      (node (ref "R2733") (pin "1") (pinfunction "1_1") (pintype "passive"))
      (node (ref "U719") (pin "65") (pinfunction "EP_PAD_65") (pintype "passive"))
      (node (ref "U720") (pin "3") (pinfunction "GND1_3") (pintype "passive"))
      (node (ref "U720") (pin "8") (pinfunction "GND2_8") (pintype "passive"))
      (node (ref "U721") (pin "3") (pinfunction "GND1_3") (pintype "passive"))
      (node (ref "U721") (pin "8") (pinfunction "GND2_8") (pintype "passive"))
      (node (ref "Y404") (pin "2") (pinfunction "2_2") (pintype "passive"))
      (node (ref "Y404") (pin "4") (pinfunction "4_4") (pintype "passive"))
    )
    (net (code "34") (name "HDMI_5V") (class "Default")
      (node (ref "C913") (pin "1") (pinfunction "1_1") (pintype "passive"))
      (node (ref "D609") (pin "1") (pinfunction "1_1") (pintype "passive"))
      (node (ref "F5") (pin "2") (pinfunction "2_2") (pintype "passive"))
      (node (ref "P5") (pin "18") (pinfunction "+5V_18") (pintype "passive"))
      (node (ref "R2730") (pin "1") (pinfunction "1_1") (pintype "passive"))
      (node (ref "R2732") (pin "1") (pinfunction "1_1") (pintype "passive"))
    )
    (net (code "35") (name "I2C1_SCL") (class "Default")
      (node (ref "R2725") (pin "2") (pinfunction "2_2") (pintype "passive"))
    )
    (net (code "36") (name "I2C1_SDA") (class "Default")
      (node (ref "R2726") (pin "2") (pinfunction "2_2") (pintype "passive"))
    )
    (net (code "37") (name "I2C4_SCL") (class "Default")
      (node (ref "R2996") (pin "2") (pinfunction "2_2") (pintype "passive"))
    )
    (net (code "38") (name "I2C4_SDA") (class "Default")
      (node (ref "R2997") (pin "2") (pinfunction "2_2") (pintype "passive"))
    )
    (net (code "39") (name "IVDD_1V8") (class "Default")
      (node (ref "C891") (pin "1") (pinfunction "1_1") (pintype "passive"))
      (node (ref "C892") (pin "1") (pinfunction "1_1") (pintype "passive"))
      (node (ref "C893") (pin "1") (pinfunction "1_1") (pintype "passive"))
      (node (ref "C894") (pin "1") (pinfunction "1_1") (pintype "passive"))
      (node (ref "C895") (pin "1") (pinfunction "1_1") (pintype "passive"))
      (node (ref "FB26") (pin "2") (pinfunction "2_2") (pintype "passive"))
      (node (ref "U719") (pin "10") (pinfunction "IVDD1_10") (pintype "passive"))
      (node (ref "U719") (pin "35") (pinfunction "IVDD2_35") (pintype "passive"))
      (node (ref "U719") (pin "49") (pinfunction "IVDD3_49") (pintype "passive"))
      (node (ref "U719") (pin "64") (pinfunction "IVDD4_64") (pintype "passive"))
    )
    (net (code "40") (name "LVDS_nRST") (class "Default")
      (node (ref "R2731") (pin "2") (pinfunction "2_2") (pintype "passive"))
    )
    (net (code "41") (name "Net-(U719-PCSCL)") (class "Default")
      (node (ref "R2725") (pin "1") (pinfunction "1_1") (pintype "passive"))
      (node (ref "R2996") (pin "1") (pinfunction "1_1") (pintype "passive"))
      (node (ref "U719") (pin "15") (pinfunction "PCSCL_15") (pintype "passive"))
    )
    (net (code "42") (name "Net-(U719-PCSDA)") (class "Default")
      (node (ref "R2726") (pin "1") (pinfunction "1_1") (pintype "passive"))
      (node (ref "R2997") (pin "1") (pinfunction "1_1") (pintype "passive"))
      (node (ref "U719") (pin "16") (pinfunction "PCSDA_16") (pintype "passive"))
    )
    (net (code "43") (name "Net-(U722-C)") (class "Default")
      (node (ref "F5") (pin "1") (pinfunction "1_1") (pintype "passive"))
      (node (ref "U722") (pin "2") (pinfunction "C_2") (pintype "passive"))
    )
    (net (code "44") (name "OVDD_3V3") (class "Default")
      (node (ref "C887") (pin "1") (pinfunction "1_1") (pintype "passive"))
      (node (ref "C888") (pin "1") (pinfunction "1_1") (pintype "passive"))
      (node (ref "FB24") (pin "2") (pinfunction "2_2") (pintype "passive"))
      (node (ref "U719") (pin "11") (pinfunction "OVDD_11") (pintype "passive"))
    )
    (net (code "45") (name "PVCC1_1V8") (class "Default")
      (node (ref "C889") (pin "1") (pinfunction "1_1") (pintype "passive"))
      (node (ref "C890") (pin "1") (pinfunction "1_1") (pintype "passive"))
      (node (ref "FB25") (pin "2") (pinfunction "2_2") (pintype "passive"))
      (node (ref "U719") (pin "51") (pinfunction "PVCC1_51") (pintype "passive"))
    )
    (net (code "46") (name "PVCC2_1V8") (class "Default")
      (node (ref "C901") (pin "1") (pinfunction "1_1") (pintype "passive"))
      (node (ref "C902") (pin "1") (pinfunction "1_1") (pintype "passive"))
      (node (ref "FB29") (pin "2") (pinfunction "2_2") (pintype "passive"))
      (node (ref "U719") (pin "62") (pinfunction "PVCC2_62") (pintype "passive"))
    )
    (net (code "47") (name "TXAVCC_1V8") (class "Default")
      (node (ref "C908") (pin "1") (pinfunction "1_1") (pintype "passive"))
      (node (ref "C909") (pin "1") (pinfunction "1_1") (pintype "passive"))
      (node (ref "C910") (pin "1") (pinfunction "1_1") (pintype "passive"))
      (node (ref "FB31") (pin "2") (pinfunction "2_2") (pintype "passive"))
      (node (ref "R2720") (pin "2") (pinfunction "2_2") (pintype "passive"))
      (node (ref "U719") (pin "54") (pinfunction "TXAVCC18_1_54") (pintype "passive"))
      (node (ref "U719") (pin "59") (pinfunction "TXAVCC18_2_59") (pintype "passive"))
    )
    (net (code "48") (name "TXAVCC_3V3") (class "Default")
      (node (ref "C885") (pin "1") (pinfunction "1_1") (pintype "passive"))
      (node (ref "C886") (pin "1") (pinfunction "1_1") (pintype "passive"))
      (node (ref "FB23") (pin "2") (pinfunction "2_2") (pintype "passive"))
      (node (ref "U719") (pin "63") (pinfunction "TXAVCC33_63") (pintype "passive"))
    )
    (net (code "49") (name "VDD_1V8") (class "Default")
      (node (ref "FB25") (pin "1") (pinfunction "1_1") (pintype "passive"))
      (node (ref "FB26") (pin "1") (pinfunction "1_1") (pintype "passive"))
      (node (ref "FB27") (pin "1") (pinfunction "1_1") (pintype "passive"))
      (node (ref "FB29") (pin "1") (pinfunction "1_1") (pintype "passive"))
      (node (ref "FB30") (pin "1") (pinfunction "1_1") (pintype "passive"))
      (node (ref "FB31") (pin "1") (pinfunction "1_1") (pintype "passive"))
    )
    (net (code "50") (name "VDD_3V3") (class "Default")
      (node (ref "FB23") (pin "1") (pinfunction "1_1") (pintype "passive"))
      (node (ref "FB24") (pin "1") (pinfunction "1_1") (pintype "passive"))
      (node (ref "FB28") (pin "1") (pinfunction "1_1") (pintype "passive"))
      (node (ref "R2729") (pin "2") (pinfunction "2_2") (pintype "passive"))
    )
    (net (code "51") (name "VDD_5V") (class "Default")
      (node (ref "C911") (pin "1") (pinfunction "1_1") (pintype "passive"))
      (node (ref "C912") (pin "1") (pinfunction "1_1") (pintype "passive"))
      (node (ref "U722") (pin "1") (pinfunction "A_1") (pintype "passive"))
    )
    (net (code "52") (name "unconnected-(P5-CEC-Pad13)") (class "Default")
      (node (ref "P5") (pin "13") (pinfunction "CEC_13") (pintype "passive+no_connect"))
    )
    (net (code "53") (name "unconnected-(P5-Utility-Pad14)") (class "Default")
      (node (ref "P5") (pin "14") (pinfunction "Utility_14") (pintype "passive+no_connect"))
    )
    (net (code "54") (name "unconnected-(U719-I2S0-Pad9)") (class "Default")
      (node (ref "U719") (pin "9") (pinfunction "I2S0_9") (pintype "passive+no_connect"))
    )
    (net (code "55") (name "unconnected-(U719-I2S1-Pad8)") (class "Default")
      (node (ref "U719") (pin "8") (pinfunction "I2S1_8") (pintype "passive+no_connect"))
    )
    (net (code "56") (name "unconnected-(U719-I2S2-Pad7)") (class "Default")
      (node (ref "U719") (pin "7") (pinfunction "I2S2_7") (pintype "passive+no_connect"))
    )
    (net (code "57") (name "unconnected-(U719-I2S3-Pad6)") (class "Default")
      (node (ref "U719") (pin "6") (pinfunction "I2S3_6") (pintype "passive+no_connect"))
    )
    (net (code "58") (name "unconnected-(U719-RXNA2-Pad37)") (class "Default")
      (node (ref "U719") (pin "37") (pinfunction "RXNA2_37") (pintype "passive+no_connect"))
    )
    (net (code "59") (name "unconnected-(U719-RXNB2-Pad39)") (class "Default")
      (node (ref "U719") (pin "39") (pinfunction "RXNB2_39") (pintype "passive+no_connect"))
    )
    (net (code "60") (name "unconnected-(U719-RXNC2-Pad42)") (class "Default")
      (node (ref "U719") (pin "42") (pinfunction "RXNC2_42") (pintype "passive+no_connect"))
    )
    (net (code "61") (name "unconnected-(U719-RXND2-Pad45)") (class "Default")
      (node (ref "U719") (pin "45") (pinfunction "RXND2_45") (pintype "passive+no_connect"))
    )
    (net (code "62") (name "unconnected-(U719-RXNE1-Pad30)") (class "Default")
      (node (ref "U719") (pin "30") (pinfunction "RXNE1_30") (pintype "passive+no_connect"))
    )
    (net (code "63") (name "unconnected-(U719-RXNE2-Pad47)") (class "Default")
      (node (ref "U719") (pin "47") (pinfunction "RXNE2_47") (pintype "passive+no_connect"))
    )
    (net (code "64") (name "unconnected-(U719-RXPA2-Pad38)") (class "Default")
      (node (ref "U719") (pin "38") (pinfunction "RXPA2_38") (pintype "passive+no_connect"))
    )
    (net (code "65") (name "unconnected-(U719-RXPB2-Pad40)") (class "Default")
      (node (ref "U719") (pin "40") (pinfunction "RXPB2_40") (pintype "passive+no_connect"))
    )
    (net (code "66") (name "unconnected-(U719-RXPC2-Pad43)") (class "Default")
      (node (ref "U719") (pin "43") (pinfunction "RXPC2_43") (pintype "passive+no_connect"))
    )
    (net (code "67") (name "unconnected-(U719-RXPD2-Pad46)") (class "Default")
      (node (ref "U719") (pin "46") (pinfunction "RXPD2_46") (pintype "passive+no_connect"))
    )
    (net (code "68") (name "unconnected-(U719-RXPE1-Pad31)") (class "Default")
      (node (ref "U719") (pin "31") (pinfunction "RXPE1_31") (pintype "passive+no_connect"))
    )
    (net (code "69") (name "unconnected-(U719-RXPE2-Pad48)") (class "Default")
      (node (ref "U719") (pin "48") (pinfunction "RXPE2_48") (pintype "passive+no_connect"))
    )
    (net (code "70") (name "unconnected-(U719-SCL_MCLK-Pad13)") (class "Default")
      (node (ref "U719") (pin "13") (pinfunction "SCL_MCLK_13") (pintype "passive+no_connect"))
    )
    (net (code "71") (name "unconnected-(U719-WS_SPDIF-Pad12)") (class "Default")
      (node (ref "U719") (pin "12") (pinfunction "WS_SPDIF_12") (pintype "passive+no_connect"))
    )
  )
)
